# Power.net
KiCad netlist of a schematic drawn in Altium Designer
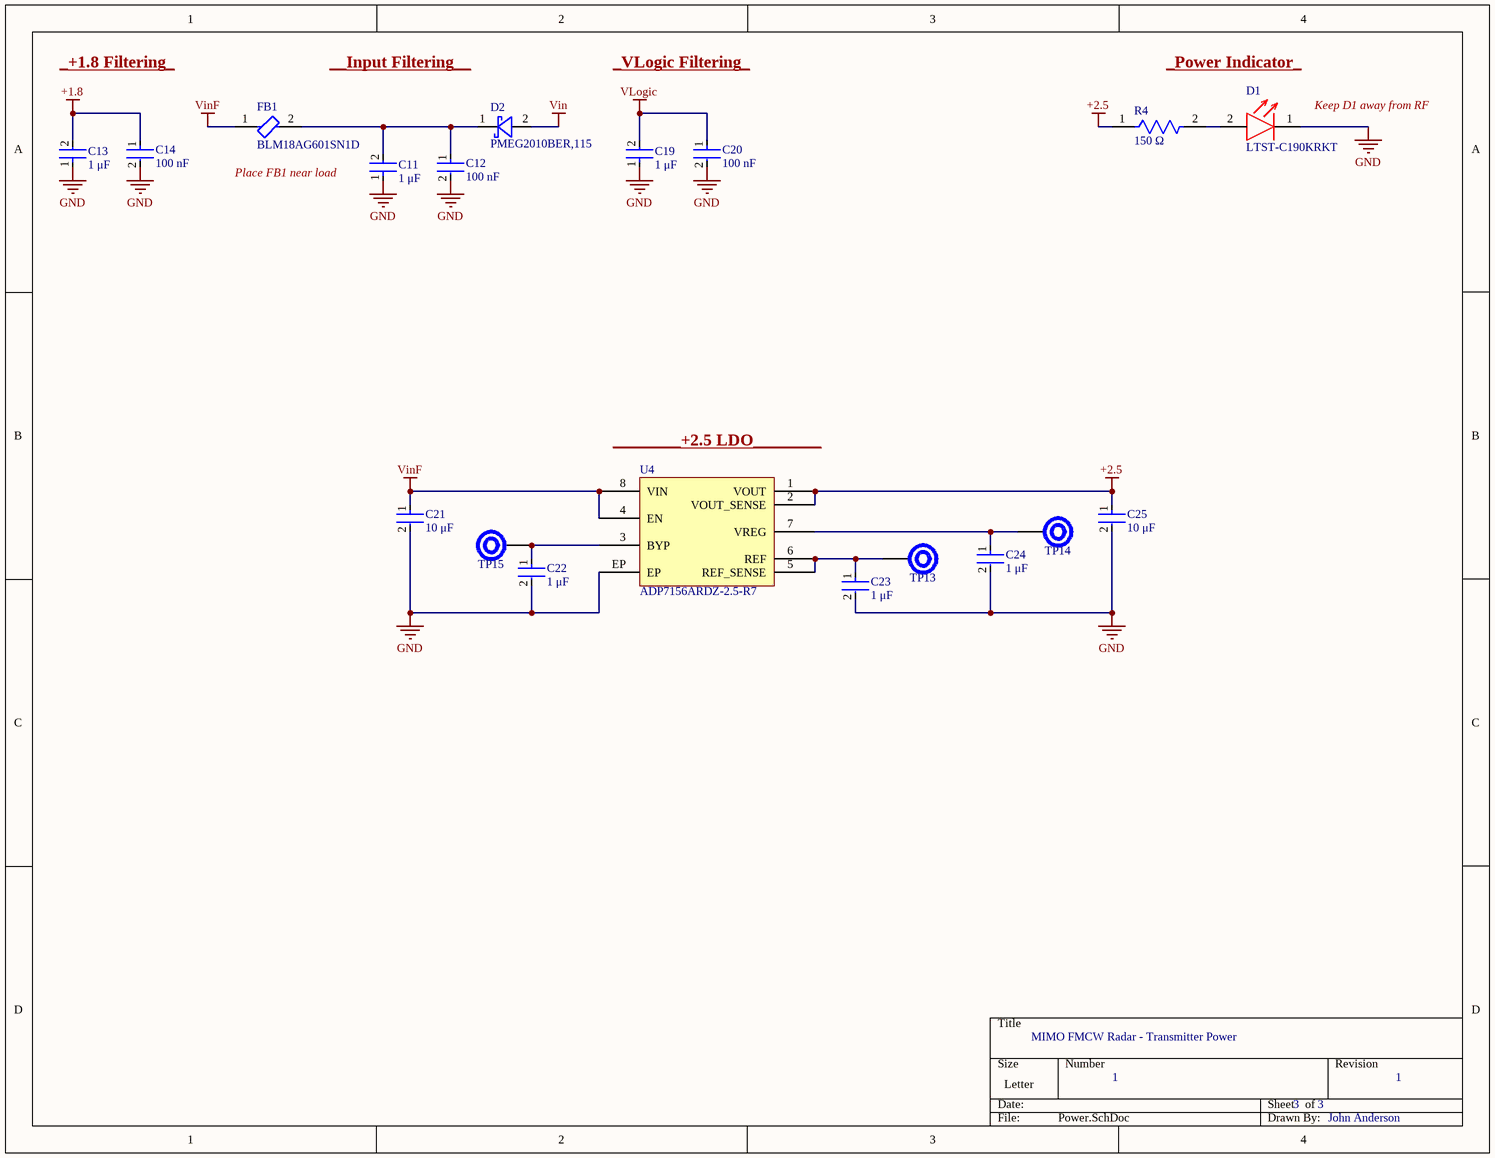
[diagram p0: Power.SchDoc]

(export (version "E")
  (design (tool "Eeschema 10.0.6"))
  (components
    (comp (ref "C11")
      (value "1 μF")
      (footprint "FP-0603-L_1_6_0_15-W_0_8-MFG")
      (libsource (lib "Power Pullers") (part "11868f565c42a9108669ba33697ecf6"))
    )
    (comp (ref "C12")
      (value "100 nF")
      (footprint "FP-CGA3E-0_3-0_1-MFG")
      (libsource (lib "Power Pullers") (part "b4654b650e69147ec39a6b967a45e02"))
    )
    (comp (ref "C13")
      (value "1 μF")
      (footprint "FP-0603-L_1_6_0_15-W_0_8-MFG")
      (libsource (lib "Power Pullers") (part "11868f565c42a9108669ba33697ecf6"))
    )
    (comp (ref "C14")
      (value "100 nF")
      (footprint "FP-CGA3E-0_3-0_1-MFG")
      (libsource (lib "Power Pullers") (part "b4654b650e69147ec39a6b967a45e02"))
    )
    (comp (ref "C19")
      (value "1 μF")
      (footprint "FP-0603-L_1_6_0_15-W_0_8-MFG")
      (libsource (lib "Power Pullers") (part "11868f565c42a9108669ba33697ecf6"))
    )
    (comp (ref "C20")
      (value "100 nF")
      (footprint "FP-CGA3E-0_3-0_1-MFG")
      (libsource (lib "Power Pullers") (part "b4654b650e69147ec39a6b967a45e02"))
    )
    (comp (ref "C21")
      (value "10 μF")
      (footprint "FP-GRM21B-0_15-IPC_C")
      (libsource (lib "Power Pullers") (part "b4654b650e69147ec39a6b967a45e02"))
    )
    (comp (ref "C22")
      (value "1 μF")
      (footprint "FP-0603-L_1_6_0_15-W_0_8-MFG")
      (libsource (lib "Power Pullers") (part "11868f565c42a9108669ba33697ecf6"))
    )
    (comp (ref "C23")
      (value "1 μF")
      (footprint "FP-0603-L_1_6_0_15-W_0_8-MFG")
      (libsource (lib "Power Pullers") (part "11868f565c42a9108669ba33697ecf6"))
    )
    (comp (ref "C24")
      (value "1 μF")
      (footprint "FP-0603-L_1_6_0_15-W_0_8-MFG")
      (libsource (lib "Power Pullers") (part "11868f565c42a9108669ba33697ecf6"))
    )
    (comp (ref "C25")
      (value "10 μF")
      (footprint "FP-GRM21B-0_15-IPC_C")
      (libsource (lib "Power Pullers") (part "b4654b650e69147ec39a6b967a45e02"))
    )
    (comp (ref "D1")
      (value "LTST-C190KRKT")
      (footprint "LTST-C190KRKT-Footprint-1")
      (description "Red, Single Color LED, Red, Water Clear")
      (libsource (lib "Power Pullers") (part "LTST-C190KRKT-Symbol-1"))
    )
    (comp (ref "D2")
      (value "PMEG2010BER,115")
      (footprint "PMEG2010BER,115-Footprint-1")
      (description "PMEG2010 Series 20 V 1 A SMT Low VF MEGA Schottky Barrier Rectifier - SOD-123W")
      (libsource (lib "Power Pullers") (part "PMEG2010BER,115-Symbol-1"))
    )
    (comp (ref "FB1")
      (value "BLM18AG601SN1D")
      (footprint "FP-BLM18-0_15-t0_8-IPC_B")
      (description "Ferrite Beads Multi-Layer 600Ohm 25% 100MHz 500mA 380mOhm DCR 0603 Automotive Paper T/R")
      (fields (field (name "TOLERANCE") "25%"))
      (libsource (lib "Power Pullers") (part "5f30dd21d616792df468990f7003faa"))
    )
    (comp (ref "R4")
      (value "150 Ω")
      (footprint "FP-RMCF0603-IPC_C")
      (description "150 Ohm, Res Thick Film 0603 1% 0.1W ±100ppm/°C Molded SMD Paper T/R")
      (fields (field (name "TOLERANCE") "1%"))
      (libsource (lib "Power Pullers") (part "1029c3af85768c4190bb7ad29bc67b5"))
    )
    (comp (ref "TP13")
      (value "Test Point - 32 mil")
      (footprint "Test Point - 32 mil-Footprint-1")
      (description "32 mil (0.8 mm) test point.")
      (libsource (lib "Power Pullers") (part "Test Point - 32 mil-Symbol-1"))
    )
    (comp (ref "TP14")
      (value "Test Point - 32 mil")
      (footprint "Test Point - 32 mil-Footprint-1")
      (description "32 mil (0.8 mm) test point.")
      (libsource (lib "Power Pullers") (part "Test Point - 32 mil-Symbol-1"))
    )
    (comp (ref "TP15")
      (value "Test Point - 32 mil")
      (footprint "Test Point - 32 mil-Footprint-1")
      (description "32 mil (0.8 mm) test point.")
      (libsource (lib "Power Pullers") (part "Test Point - 32 mil-Symbol-1"))
    )
    (comp (ref "U4")
      (value "ADP7156ARDZ-2.5-R7")
      (footprint "ADP7156ARDZ-2.5-R7-Footprint-1")
      (description "LDO Regulator Pos 2.5V 1.2A 8-Pin SOIC N EP T/R")
      (libsource (lib "Power Pullers") (part "ADP7156ARDZ-2.5-R7-Symbol-1"))
    )
  )
  (nets
    (net (code "1") (name "+1.8") (class "Default")
      (node (ref "C13") (pin "2") (pinfunction "2_2") (pintype "passive"))
      (node (ref "C14") (pin "1") (pinfunction "1_1") (pintype "passive"))
    )
    (net (code "2") (name "+2.5") (class "Default")
      (node (ref "C25") (pin "1") (pinfunction "1_1") (pintype "passive"))
      (node (ref "R4") (pin "1") (pinfunction "1_1") (pintype "passive"))
      (node (ref "U4") (pin "1") (pinfunction "VOUT_1") (pintype "passive"))
      (node (ref "U4") (pin "2") (pinfunction "VOUT_SENSE_2") (pintype "passive"))
    )
    (net (code "3") (name "GND") (class "Default")
      (node (ref "C11") (pin "1") (pinfunction "1_1") (pintype "passive"))
      (node (ref "C12") (pin "2") (pinfunction "2_2") (pintype "passive"))
      (node (ref "C13") (pin "1") (pinfunction "1_1") (pintype "passive"))
      (node (ref "C14") (pin "2") (pinfunction "2_2") (pintype "passive"))
      (node (ref "C19") (pin "1") (pinfunction "1_1") (pintype "passive"))
      (node (ref "C20") (pin "2") (pinfunction "2_2") (pintype "passive"))
      (node (ref "C21") (pin "2") (pinfunction "2_2") (pintype "passive"))
      (node (ref "C22") (pin "2") (pinfunction "2_2") (pintype "passive"))
      (node (ref "C23") (pin "2") (pinfunction "2_2") (pintype "passive"))
      (node (ref "C24") (pin "2") (pinfunction "2_2") (pintype "passive"))
      (node (ref "C25") (pin "2") (pinfunction "2_2") (pintype "passive"))
      (node (ref "D1") (pin "1") (pinfunction "1_1") (pintype "passive"))
      (node (ref "U4") (pin "EP") (pinfunction "EP_EP") (pintype "passive"))
    )
    (net (code "4") (name "Net-(C11-Pad2)") (class "Default")
      (node (ref "C11") (pin "2") (pinfunction "2_2") (pintype "passive"))
      (node (ref "C12") (pin "1") (pinfunction "1_1") (pintype "passive"))
      (node (ref "D2") (pin "1") (pinfunction "1_1") (pintype "passive"))
      (node (ref "FB1") (pin "2") (pinfunction "2_2") (pintype "passive"))
    )
    (net (code "5") (name "Net-(D1-Pad2)") (class "Default")
      (node (ref "D1") (pin "2") (pinfunction "2_2") (pintype "passive"))
      (node (ref "R4") (pin "2") (pinfunction "2_2") (pintype "passive"))
    )
    (net (code "6") (name "Net-(U4-BYP)") (class "Default")
      (node (ref "C22") (pin "1") (pinfunction "1_1") (pintype "passive"))
      (node (ref "TP15") (pin "1") (pinfunction "1_1") (pintype "passive"))
      (node (ref "U4") (pin "3") (pinfunction "BYP_3") (pintype "passive"))
    )
    (net (code "7") (name "Net-(U4-REF)") (class "Default")
      (node (ref "C23") (pin "1") (pinfunction "1_1") (pintype "passive"))
      (node (ref "TP13") (pin "1") (pinfunction "1_1") (pintype "passive"))
      (node (ref "U4") (pin "5") (pinfunction "REF_SENSE_5") (pintype "passive"))
      (node (ref "U4") (pin "6") (pinfunction "REF_6") (pintype "passive"))
    )
    (net (code "8") (name "Net-(U4-VREG)") (class "Default")
      (node (ref "C24") (pin "1") (pinfunction "1_1") (pintype "passive"))
      (node (ref "TP14") (pin "1") (pinfunction "1_1") (pintype "passive"))
      (node (ref "U4") (pin "7") (pinfunction "VREG_7") (pintype "passive"))
    )
    (net (code "9") (name "VLogic") (class "Default")
      (node (ref "C19") (pin "2") (pinfunction "2_2") (pintype "passive"))
      (node (ref "C20") (pin "1") (pinfunction "1_1") (pintype "passive"))
    )
    (net (code "10") (name "Vin") (class "Default")
      (node (ref "D2") (pin "2") (pinfunction "2_2") (pintype "passive"))
    )
    (net (code "11") (name "VinF") (class "Default")
      (node (ref "C21") (pin "1") (pinfunction "1_1") (pintype "passive"))
      (node (ref "FB1") (pin "1") (pinfunction "1_1") (pintype "passive"))
      (node (ref "U4") (pin "4") (pinfunction "EN_4") (pintype "passive"))
      (node (ref "U4") (pin "8") (pinfunction "VIN_8") (pintype "passive"))
    )
  )
)
